# battery_gauge_max17043g_u.net
KiCad netlist of a schematic drawn in EAGLE
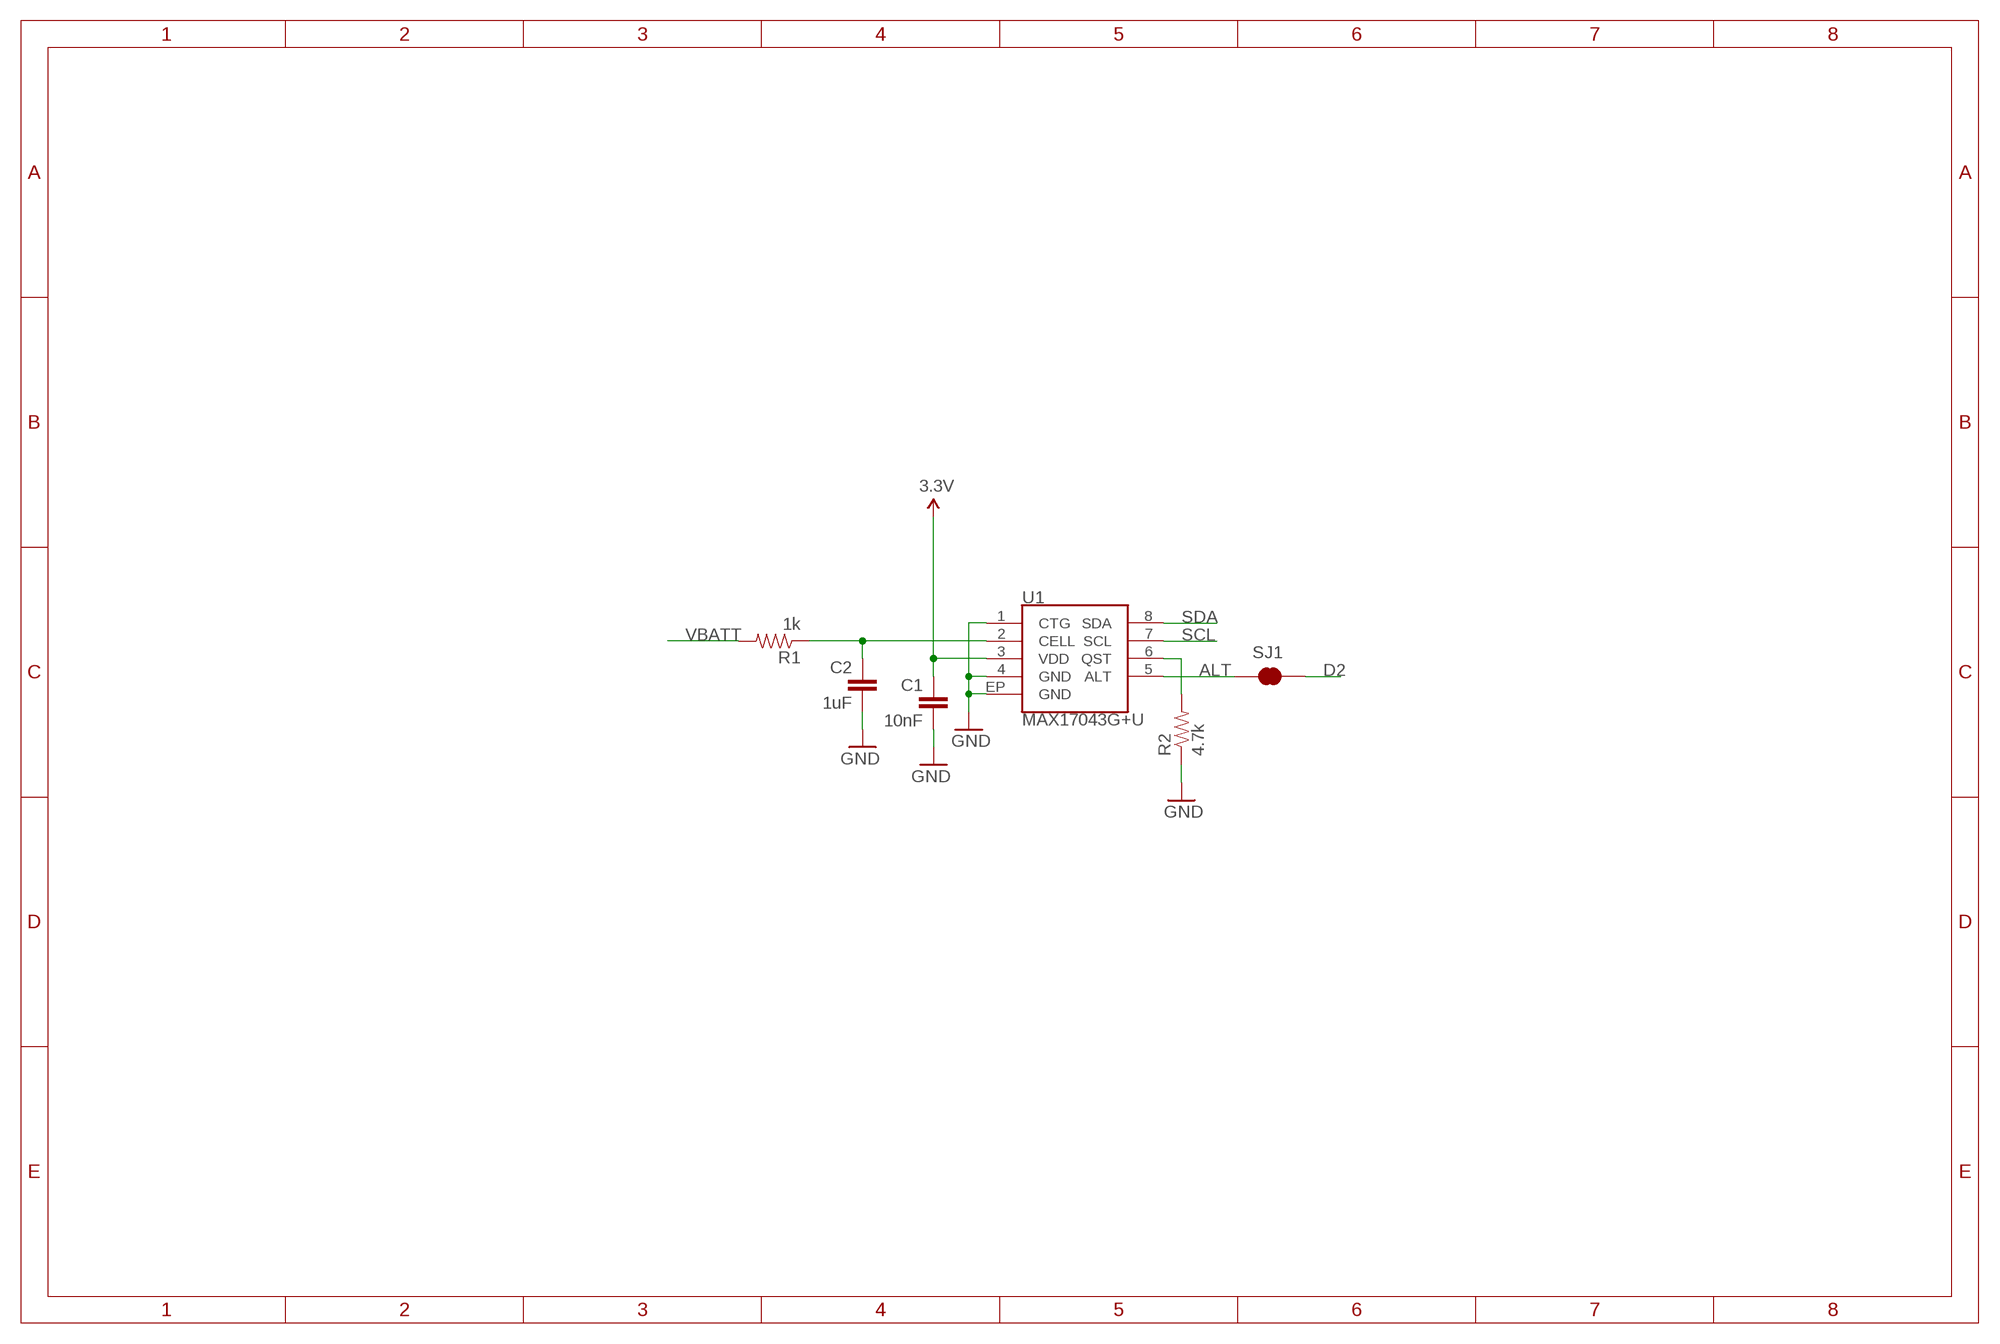
[diagram p0: schematic, sheet 1]

(export (version "E")
  (design (tool "Eeschema 10.0.6"))
  (components
    (comp (ref "C1")
      (value "10nF")
      (footprint "eagle-import:0402-CAP")
      (libsource (lib "eagle-import") (part "CAP0402-CAP"))
    )
    (comp (ref "C2")
      (value "1uF")
      (footprint "eagle-import:0402-CAP")
      (libsource (lib "eagle-import") (part "CAP0402-CAP"))
    )
    (comp (ref "R1")
      (value "1k")
      (footprint "eagle-import:0402-RES")
      (libsource (lib "eagle-import") (part "RESISTOR0402-RES"))
    )
    (comp (ref "R2")
      (value "4.7k")
      (footprint "eagle-import:0402-RES")
      (libsource (lib "eagle-import") (part "RESISTOR0402-RES"))
    )
    (comp (ref "SJ1")
      (value "SOLDERJUMPERTRACE")
      (footprint "eagle-import:SJ_2S-TRACE")
      (libsource (lib "eagle-import") (part "SOLDERJUMPERTRACE"))
    )
    (comp (ref "U1")
      (value "MAX17043G+U")
      (footprint "eagle-import:TDFN-8")
      (libsource (lib "eagle-import") (part "MAX1704X"))
    )
  )
  (nets
    (net (code "1") (name "/ALT") (class "Default")
      (node (ref "SJ1") (pin "1") (pinfunction "1_1") (pintype "passive"))
      (node (ref "U1") (pin "5") (pinfunction "ALT_5") (pintype "bidirectional"))
    )
    (net (code "2") (name "/D2") (class "Default")
      (node (ref "SJ1") (pin "2") (pinfunction "2_2") (pintype "passive"))
    )
    (net (code "3") (name "/SCL") (class "Default")
      (node (ref "U1") (pin "7") (pinfunction "SCL_7") (pintype "bidirectional"))
    )
    (net (code "4") (name "/SDA") (class "Default")
      (node (ref "U1") (pin "8") (pinfunction "SDA_8") (pintype "bidirectional"))
    )
    (net (code "5") (name "/VBATT") (class "Default")
      (node (ref "R1") (pin "2") (pinfunction "2_2") (pintype "passive"))
    )
    (net (code "6") (name "3.3V") (class "Default")
      (node (ref "C1") (pin "1") (pinfunction "1_1") (pintype "passive"))
      (node (ref "U1") (pin "3") (pinfunction "VDD_3") (pintype "bidirectional"))
    )
    (net (code "7") (name "GND") (class "Default")
      (node (ref "C1") (pin "2") (pinfunction "2_2") (pintype "passive"))
      (node (ref "C2") (pin "2") (pinfunction "2_2") (pintype "passive"))
      (node (ref "R2") (pin "1") (pinfunction "1_1") (pintype "passive"))
      (node (ref "U1") (pin "1") (pinfunction "CTG_1") (pintype "bidirectional"))
      (node (ref "U1") (pin "4") (pinfunction "GND_4") (pintype "bidirectional"))
      (node (ref "U1") (pin "EP") (pinfunction "GND_EP") (pintype "bidirectional"))
    )
    (net (code "8") (name "Net-(U1-CELL)") (class "Default")
      (node (ref "C2") (pin "1") (pinfunction "1_1") (pintype "passive"))
      (node (ref "R1") (pin "1") (pinfunction "1_1") (pintype "passive"))
      (node (ref "U1") (pin "2") (pinfunction "CELL_2") (pintype "bidirectional"))
    )
    (net (code "9") (name "Net-(U1-QST)") (class "Default")
      (node (ref "R2") (pin "2") (pinfunction "2_2") (pintype "passive"))
      (node (ref "U1") (pin "6") (pinfunction "QST_6") (pintype "bidirectional"))
    )
  )
)
